# Analog_Teil.net
KiCad netlist of a schematic drawn in EAGLE
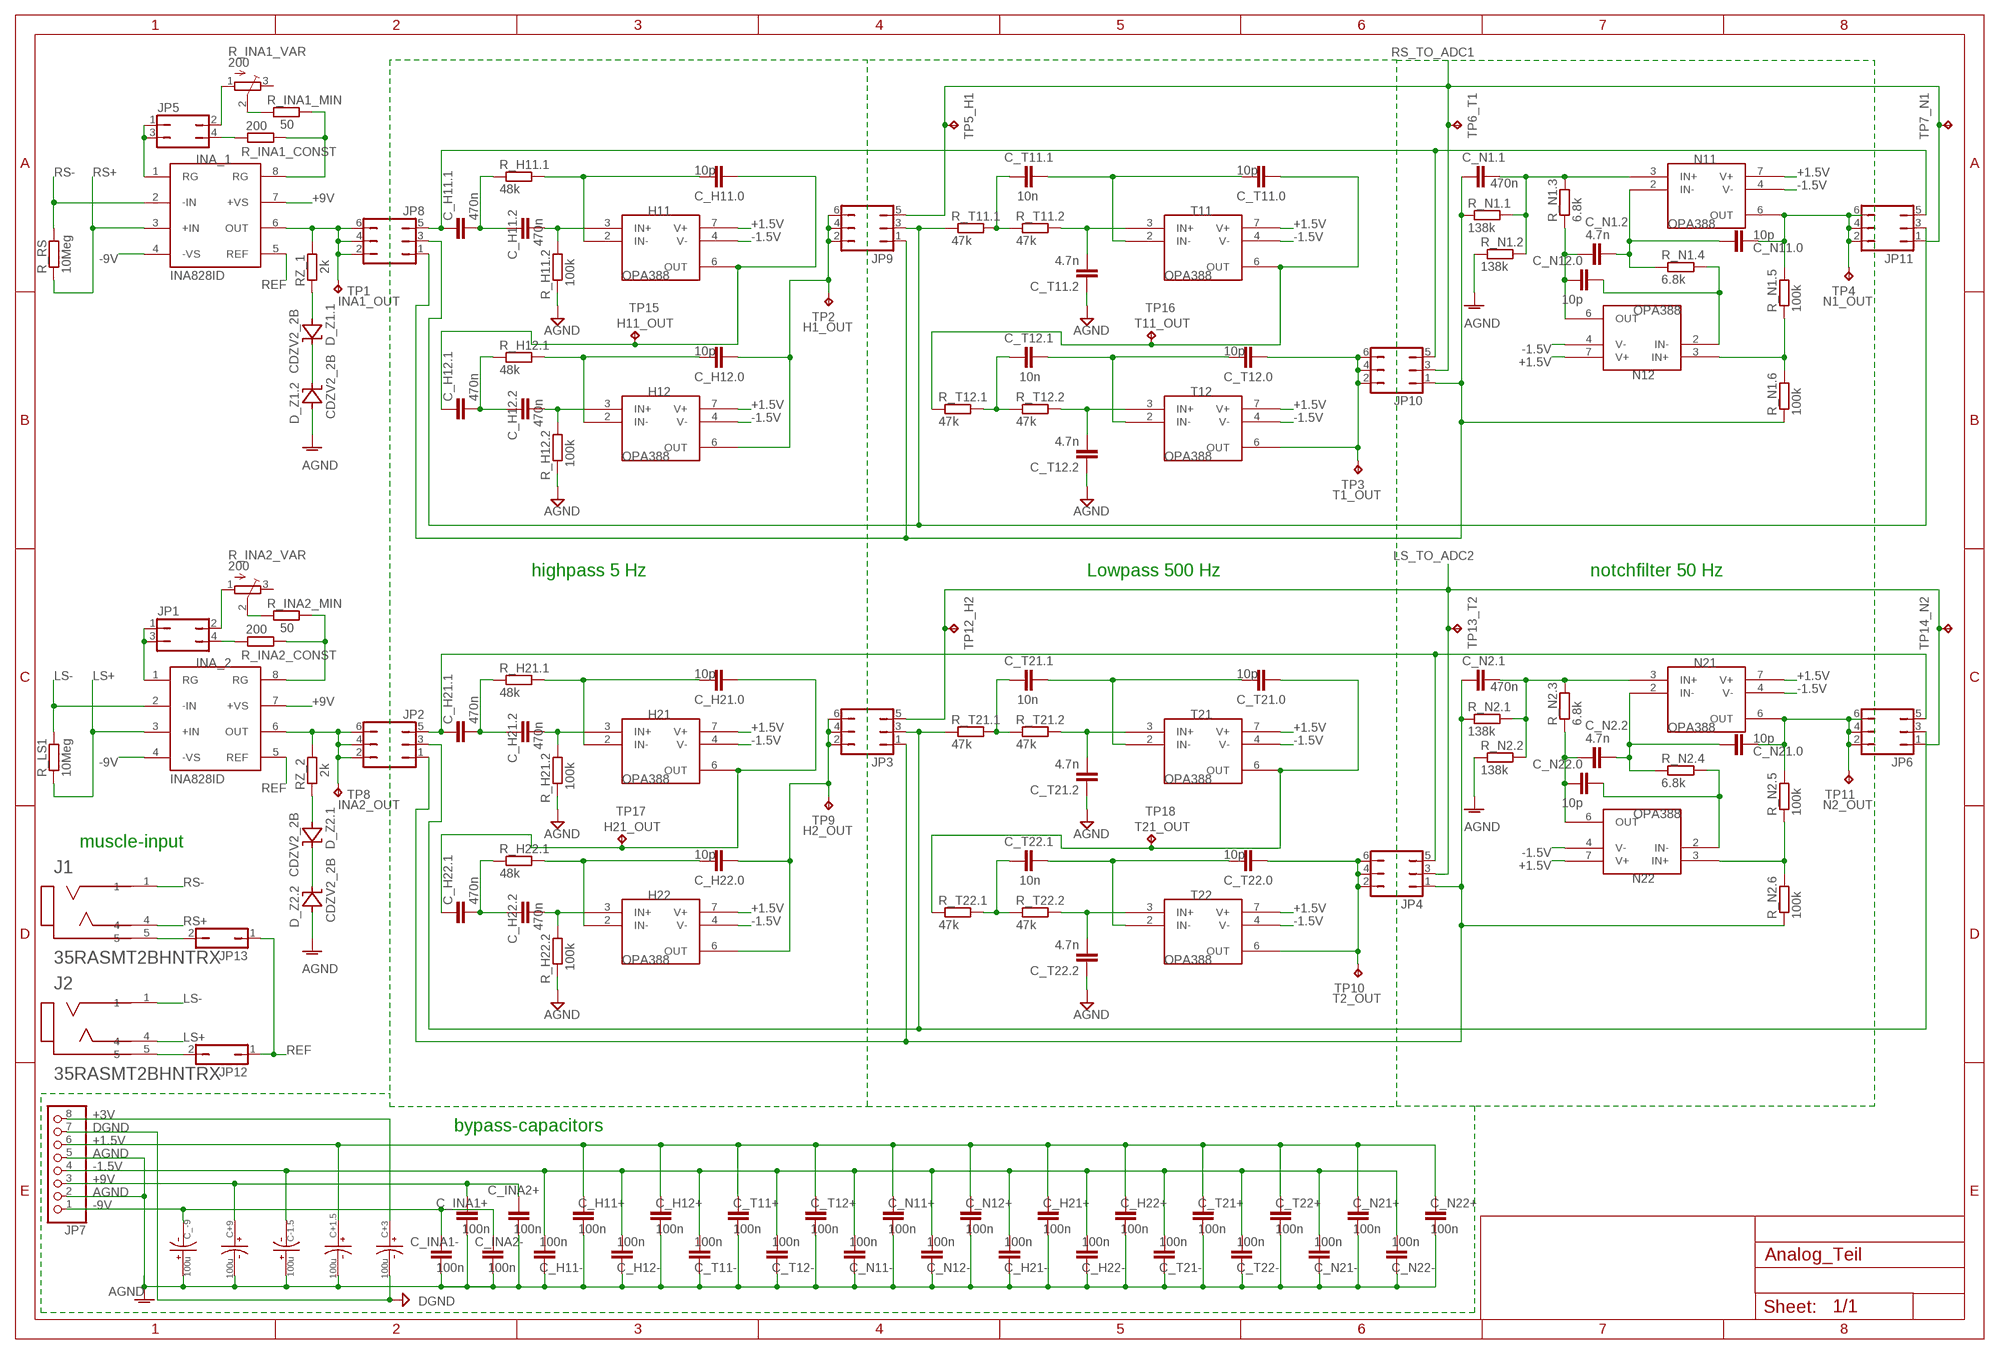
[diagram p0: schematic, sheet 1]

(export (version "E")
  (design (tool "Eeschema 10.0.6"))
  (components
    (comp (ref "C+1.5")
      (value "100u")
      (footprint "eagle-import:CAPPRD350W60D800H1150B")
      (fields (field (name "MF") "Panasonic Electronic") (field (name "MP") "ECA1HM101"))
      (libsource (lib "eagle-import") (part "ECA-1HM101"))
    )
    (comp (ref "C+3")
      (value "100u")
      (footprint "eagle-import:CAPPRD350W60D800H1150B")
      (fields (field (name "MF") "Panasonic Electronic") (field (name "MP") "ECA1HM101"))
      (libsource (lib "eagle-import") (part "ECA-1HM101"))
    )
    (comp (ref "C+9")
      (value "100u")
      (footprint "eagle-import:CAPPRD350W60D800H1150B")
      (fields (field (name "MF") "Panasonic Electronic") (field (name "MP") "ECA1HM101"))
      (libsource (lib "eagle-import") (part "ECA-1HM101"))
    )
    (comp (ref "C-1.5")
      (value "100u")
      (footprint "eagle-import:CAPPRD350W60D800H1150B")
      (fields (field (name "MF") "Panasonic Electronic") (field (name "MP") "ECA1HM101"))
      (libsource (lib "eagle-import") (part "ECA-1HM101"))
    )
    (comp (ref "C_-9")
      (value "100u")
      (footprint "eagle-import:CAPPRD350W60D800H1150B")
      (fields (field (name "MF") "Panasonic Electronic") (field (name "MP") "ECA1HM101"))
      (libsource (lib "eagle-import") (part "ECA-1HM101"))
    )
    (comp (ref "C_H11+")
      (value "100n")
      (footprint "eagle-import:C0805")
      (libsource (lib "eagle-import") (part "C-EUC0805"))
    )
    (comp (ref "C_H11-")
      (value "100n")
      (footprint "eagle-import:C0805")
      (libsource (lib "eagle-import") (part "C-EUC0805"))
    )
    (comp (ref "C_H11.0")
      (value "10p")
      (footprint "eagle-import:C0805")
      (libsource (lib "eagle-import") (part "C-EUC0805"))
    )
    (comp (ref "C_H11.1")
      (value "470n")
      (footprint "eagle-import:C0805")
      (libsource (lib "eagle-import") (part "C-EUC0805"))
    )
    (comp (ref "C_H11.2")
      (value "470n")
      (footprint "eagle-import:C0805")
      (libsource (lib "eagle-import") (part "C-EUC0805"))
    )
    (comp (ref "C_H12+")
      (value "100n")
      (footprint "eagle-import:C0805")
      (libsource (lib "eagle-import") (part "C-EUC0805"))
    )
    (comp (ref "C_H12-")
      (value "100n")
      (footprint "eagle-import:C0805")
      (libsource (lib "eagle-import") (part "C-EUC0805"))
    )
    (comp (ref "C_H12.0")
      (value "10p")
      (footprint "eagle-import:C0805")
      (libsource (lib "eagle-import") (part "C-EUC0805"))
    )
    (comp (ref "C_H12.1")
      (value "470n")
      (footprint "eagle-import:C0805")
      (libsource (lib "eagle-import") (part "C-EUC0805"))
    )
    (comp (ref "C_H12.2")
      (value "470n")
      (footprint "eagle-import:C0805")
      (libsource (lib "eagle-import") (part "C-EUC0805"))
    )
    (comp (ref "C_H21+")
      (value "100n")
      (footprint "eagle-import:C0805")
      (libsource (lib "eagle-import") (part "C-EUC0805"))
    )
    (comp (ref "C_H21-")
      (value "100n")
      (footprint "eagle-import:C0805")
      (libsource (lib "eagle-import") (part "C-EUC0805"))
    )
    (comp (ref "C_H21.0")
      (value "10p")
      (footprint "eagle-import:C0805")
      (libsource (lib "eagle-import") (part "C-EUC0805"))
    )
    (comp (ref "C_H21.1")
      (value "470n")
      (footprint "eagle-import:C0805")
      (libsource (lib "eagle-import") (part "C-EUC0805"))
    )
    (comp (ref "C_H21.2")
      (value "470n")
      (footprint "eagle-import:C0805")
      (libsource (lib "eagle-import") (part "C-EUC0805"))
    )
    (comp (ref "C_H22+")
      (value "100n")
      (footprint "eagle-import:C0805")
      (libsource (lib "eagle-import") (part "C-EUC0805"))
    )
    (comp (ref "C_H22-")
      (value "100n")
      (footprint "eagle-import:C0805")
      (libsource (lib "eagle-import") (part "C-EUC0805"))
    )
    (comp (ref "C_H22.0")
      (value "10p")
      (footprint "eagle-import:C0805")
      (libsource (lib "eagle-import") (part "C-EUC0805"))
    )
    (comp (ref "C_H22.1")
      (value "470n")
      (footprint "eagle-import:C0805")
      (libsource (lib "eagle-import") (part "C-EUC0805"))
    )
    (comp (ref "C_H22.2")
      (value "470n")
      (footprint "eagle-import:C0805")
      (libsource (lib "eagle-import") (part "C-EUC0805"))
    )
    (comp (ref "C_INA1+")
      (value "100n")
      (footprint "eagle-import:C0805")
      (libsource (lib "eagle-import") (part "C-EUC0805"))
    )
    (comp (ref "C_INA1-")
      (value "100n")
      (footprint "eagle-import:C0805")
      (libsource (lib "eagle-import") (part "C-EUC0805"))
    )
    (comp (ref "C_INA2+")
      (value "100n")
      (footprint "eagle-import:C0805")
      (libsource (lib "eagle-import") (part "C-EUC0805"))
    )
    (comp (ref "C_INA2-")
      (value "100n")
      (footprint "eagle-import:C0805")
      (libsource (lib "eagle-import") (part "C-EUC0805"))
    )
    (comp (ref "C_N1.1")
      (value "470n")
      (footprint "eagle-import:C0805")
      (libsource (lib "eagle-import") (part "C-EUC0805"))
    )
    (comp (ref "C_N1.2")
      (value "4.7n")
      (footprint "eagle-import:C0805")
      (libsource (lib "eagle-import") (part "C-EUC0805"))
    )
    (comp (ref "C_N2.1")
      (value "470n")
      (footprint "eagle-import:C0805")
      (libsource (lib "eagle-import") (part "C-EUC0805"))
    )
    (comp (ref "C_N2.2")
      (value "4.7n")
      (footprint "eagle-import:C0805")
      (libsource (lib "eagle-import") (part "C-EUC0805"))
    )
    (comp (ref "C_N11+")
      (value "100n")
      (footprint "eagle-import:C0805")
      (libsource (lib "eagle-import") (part "C-EUC0805"))
    )
    (comp (ref "C_N11-")
      (value "100n")
      (footprint "eagle-import:C0805")
      (libsource (lib "eagle-import") (part "C-EUC0805"))
    )
    (comp (ref "C_N11.0")
      (value "10p")
      (footprint "eagle-import:C0805")
      (libsource (lib "eagle-import") (part "C-EUC0805"))
    )
    (comp (ref "C_N12+")
      (value "100n")
      (footprint "eagle-import:C0805")
      (libsource (lib "eagle-import") (part "C-EUC0805"))
    )
    (comp (ref "C_N12-")
      (value "100n")
      (footprint "eagle-import:C0805")
      (libsource (lib "eagle-import") (part "C-EUC0805"))
    )
    (comp (ref "C_N12.0")
      (value "10p")
      (footprint "eagle-import:C0805")
      (libsource (lib "eagle-import") (part "C-EUC0805"))
    )
    (comp (ref "C_N21+")
      (value "100n")
      (footprint "eagle-import:C0805")
      (libsource (lib "eagle-import") (part "C-EUC0805"))
    )
    (comp (ref "C_N21-")
      (value "100n")
      (footprint "eagle-import:C0805")
      (libsource (lib "eagle-import") (part "C-EUC0805"))
    )
    (comp (ref "C_N21.0")
      (value "10p")
      (footprint "eagle-import:C0805")
      (libsource (lib "eagle-import") (part "C-EUC0805"))
    )
    (comp (ref "C_N22+")
      (value "100n")
      (footprint "eagle-import:C0805")
      (libsource (lib "eagle-import") (part "C-EUC0805"))
    )
    (comp (ref "C_N22-")
      (value "100n")
      (footprint "eagle-import:C0805")
      (libsource (lib "eagle-import") (part "C-EUC0805"))
    )
    (comp (ref "C_N22.0")
      (value "10p")
      (footprint "eagle-import:C0805")
      (libsource (lib "eagle-import") (part "C-EUC0805"))
    )
    (comp (ref "C_T11+")
      (value "100n")
      (footprint "eagle-import:C0805")
      (libsource (lib "eagle-import") (part "C-EUC0805"))
    )
    (comp (ref "C_T11-")
      (value "100n")
      (footprint "eagle-import:C0805")
      (libsource (lib "eagle-import") (part "C-EUC0805"))
    )
    (comp (ref "C_T11.0")
      (value "10p")
      (footprint "eagle-import:C0805")
      (libsource (lib "eagle-import") (part "C-EUC0805"))
    )
    (comp (ref "C_T11.1")
      (value "10n")
      (footprint "eagle-import:C0805")
      (libsource (lib "eagle-import") (part "C-EUC0805"))
    )
    (comp (ref "C_T11.2")
      (value "4.7n")
      (footprint "eagle-import:C0805")
      (libsource (lib "eagle-import") (part "C-EUC0805"))
    )
    (comp (ref "C_T12+")
      (value "100n")
      (footprint "eagle-import:C0805")
      (libsource (lib "eagle-import") (part "C-EUC0805"))
    )
    (comp (ref "C_T12-")
      (value "100n")
      (footprint "eagle-import:C0805")
      (libsource (lib "eagle-import") (part "C-EUC0805"))
    )
    (comp (ref "C_T12.0")
      (value "10p")
      (footprint "eagle-import:C0805")
      (libsource (lib "eagle-import") (part "C-EUC0805"))
    )
    (comp (ref "C_T12.1")
      (value "10n")
      (footprint "eagle-import:C0805")
      (libsource (lib "eagle-import") (part "C-EUC0805"))
    )
    (comp (ref "C_T12.2")
      (value "4.7n")
      (footprint "eagle-import:C0805")
      (libsource (lib "eagle-import") (part "C-EUC0805"))
    )
    (comp (ref "C_T21+")
      (value "100n")
      (footprint "eagle-import:C0805")
      (libsource (lib "eagle-import") (part "C-EUC0805"))
    )
    (comp (ref "C_T21-")
      (value "100n")
      (footprint "eagle-import:C0805")
      (libsource (lib "eagle-import") (part "C-EUC0805"))
    )
    (comp (ref "C_T21.0")
      (value "10p")
      (footprint "eagle-import:C0805")
      (libsource (lib "eagle-import") (part "C-EUC0805"))
    )
    (comp (ref "C_T21.1")
      (value "10n")
      (footprint "eagle-import:C0805")
      (libsource (lib "eagle-import") (part "C-EUC0805"))
    )
    (comp (ref "C_T21.2")
      (value "4.7n")
      (footprint "eagle-import:C0805")
      (libsource (lib "eagle-import") (part "C-EUC0805"))
    )
    (comp (ref "C_T22+")
      (value "100n")
      (footprint "eagle-import:C0805")
      (libsource (lib "eagle-import") (part "C-EUC0805"))
    )
    (comp (ref "C_T22-")
      (value "100n")
      (footprint "eagle-import:C0805")
      (libsource (lib "eagle-import") (part "C-EUC0805"))
    )
    (comp (ref "C_T22.0")
      (value "10p")
      (footprint "eagle-import:C0805")
      (libsource (lib "eagle-import") (part "C-EUC0805"))
    )
    (comp (ref "C_T22.1")
      (value "10n")
      (footprint "eagle-import:C0805")
      (libsource (lib "eagle-import") (part "C-EUC0805"))
    )
    (comp (ref "C_T22.2")
      (value "4.7n")
      (footprint "eagle-import:C0805")
      (libsource (lib "eagle-import") (part "C-EUC0805"))
    )
    (comp (ref "D_Z1.1")
      (value "CDZV2_2B")
      (footprint "eagle-import:SODFL1006X40N")
      (libsource (lib "eagle-import") (part "CDZV2_2BSOD923"))
    )
    (comp (ref "D_Z1.2")
      (value "CDZV2_2B")
      (footprint "eagle-import:SODFL1006X40N")
      (libsource (lib "eagle-import") (part "CDZV2_2BSOD923"))
    )
    (comp (ref "D_Z2.1")
      (value "CDZV2_2B")
      (footprint "eagle-import:SODFL1006X40N")
      (libsource (lib "eagle-import") (part "CDZV2_2BSOD923"))
    )
    (comp (ref "D_Z2.2")
      (value "CDZV2_2B")
      (footprint "eagle-import:SODFL1006X40N")
      (libsource (lib "eagle-import") (part "CDZV2_2BSOD923"))
    )
    (comp (ref "H11")
      (value "OPA388")
      (footprint "eagle-import:SOIC127P600X175-8N")
      (libsource (lib "eagle-import") (part "OPA388"))
    )
    (comp (ref "H12")
      (value "OPA388")
      (footprint "eagle-import:SOIC127P600X175-8N")
      (libsource (lib "eagle-import") (part "OPA388"))
    )
    (comp (ref "H21")
      (value "OPA388")
      (footprint "eagle-import:SOIC127P600X175-8N")
      (libsource (lib "eagle-import") (part "OPA388"))
    )
    (comp (ref "H22")
      (value "OPA388")
      (footprint "eagle-import:SOIC127P600X175-8N")
      (libsource (lib "eagle-import") (part "OPA388"))
    )
    (comp (ref "INA_1")
      (value "INA828ID")
      (footprint "eagle-import:SOIC8")
      (fields (field (name "DIGI-KEY_PART_NUMBER") "296-47415-ND") (field (name "MF") "Texas Instruments"))
      (libsource (lib "eagle-import") (part "INA828ID"))
    )
    (comp (ref "INA_2")
      (value "INA828ID")
      (footprint "eagle-import:SOIC8")
      (fields (field (name "DIGI-KEY_PART_NUMBER") "296-47415-ND") (field (name "MF") "Texas Instruments"))
      (libsource (lib "eagle-import") (part "INA828ID"))
    )
    (comp (ref "J1")
      (value "35RASMT2BHNTRX")
      (footprint "eagle-import:SWITCHCRAFT_35RASMT2BHNTRX")
      (fields (field (name "MF") "Switchcraft"))
      (libsource (lib "eagle-import") (part "35RASMT2BHNTRX"))
    )
    (comp (ref "J2")
      (value "35RASMT2BHNTRX")
      (footprint "eagle-import:SWITCHCRAFT_35RASMT2BHNTRX")
      (fields (field (name "MF") "Switchcraft"))
      (libsource (lib "eagle-import") (part "35RASMT2BHNTRX"))
    )
    (comp (ref "JP1")
      (value "JP2Q")
      (footprint "eagle-import:JP2Q")
      (libsource (lib "eagle-import") (part "JP2Q"))
    )
    (comp (ref "JP2")
      (value "JP3Q")
      (footprint "eagle-import:JP3Q")
      (libsource (lib "eagle-import") (part "JP3Q"))
    )
    (comp (ref "JP3")
      (value "JP3Q")
      (footprint "eagle-import:JP3Q")
      (libsource (lib "eagle-import") (part "JP3Q"))
    )
    (comp (ref "JP4")
      (value "JP3Q")
      (footprint "eagle-import:JP3Q")
      (libsource (lib "eagle-import") (part "JP3Q"))
    )
    (comp (ref "JP5")
      (value "JP2Q")
      (footprint "eagle-import:JP2Q")
      (libsource (lib "eagle-import") (part "JP2Q"))
    )
    (comp (ref "JP6")
      (value "JP3Q")
      (footprint "eagle-import:JP3Q")
      (libsource (lib "eagle-import") (part "JP3Q"))
    )
    (comp (ref "JP7")
      (value "PINHD-1X8")
      (footprint "eagle-import:1X08")
      (libsource (lib "eagle-import") (part "PINHD-1X8"))
    )
    (comp (ref "JP8")
      (value "JP3Q")
      (footprint "eagle-import:JP3Q")
      (libsource (lib "eagle-import") (part "JP3Q"))
    )
    (comp (ref "JP9")
      (value "JP3Q")
      (footprint "eagle-import:JP3Q")
      (libsource (lib "eagle-import") (part "JP3Q"))
    )
    (comp (ref "JP10")
      (value "JP3Q")
      (footprint "eagle-import:JP3Q")
      (libsource (lib "eagle-import") (part "JP3Q"))
    )
    (comp (ref "JP11")
      (value "JP3Q")
      (footprint "eagle-import:JP3Q")
      (libsource (lib "eagle-import") (part "JP3Q"))
    )
    (comp (ref "JP12")
      (value "JP1Q")
      (footprint "eagle-import:JP1")
      (libsource (lib "eagle-import") (part "JP1Q"))
    )
    (comp (ref "JP13")
      (value "JP1Q")
      (footprint "eagle-import:JP1")
      (libsource (lib "eagle-import") (part "JP1Q"))
    )
    (comp (ref "N11")
      (value "OPA388")
      (footprint "eagle-import:SOIC127P600X175-8N")
      (libsource (lib "eagle-import") (part "OPA388"))
    )
    (comp (ref "N12")
      (value "OPA388")
      (footprint "eagle-import:SOIC127P600X175-8N")
      (libsource (lib "eagle-import") (part "OPA388"))
    )
    (comp (ref "N21")
      (value "OPA388")
      (footprint "eagle-import:SOIC127P600X175-8N")
      (libsource (lib "eagle-import") (part "OPA388"))
    )
    (comp (ref "N22")
      (value "OPA388")
      (footprint "eagle-import:SOIC127P600X175-8N")
      (libsource (lib "eagle-import") (part "OPA388"))
    )
    (comp (ref "RZ_1")
      (value "2k")
      (footprint "eagle-import:R0805")
      (libsource (lib "eagle-import") (part "R-EU_R0805"))
    )
    (comp (ref "RZ_2")
      (value "2k")
      (footprint "eagle-import:R0805")
      (libsource (lib "eagle-import") (part "R-EU_R0805"))
    )
    (comp (ref "R_H11.1")
      (value "48k")
      (footprint "eagle-import:R0805")
      (libsource (lib "eagle-import") (part "R-EU_R0805"))
    )
    (comp (ref "R_H11.2")
      (value "100k")
      (footprint "eagle-import:R0805")
      (libsource (lib "eagle-import") (part "R-EU_R0805"))
    )
    (comp (ref "R_H12.1")
      (value "48k")
      (footprint "eagle-import:R0805")
      (libsource (lib "eagle-import") (part "R-EU_R0805"))
    )
    (comp (ref "R_H12.2")
      (value "100k")
      (footprint "eagle-import:R0805")
      (libsource (lib "eagle-import") (part "R-EU_R0805"))
    )
    (comp (ref "R_H21.1")
      (value "48k")
      (footprint "eagle-import:R0805")
      (libsource (lib "eagle-import") (part "R-EU_R0805"))
    )
    (comp (ref "R_H21.2")
      (value "100k")
      (footprint "eagle-import:R0805")
      (libsource (lib "eagle-import") (part "R-EU_R0805"))
    )
    (comp (ref "R_H22.1")
      (value "48k")
      (footprint "eagle-import:R0805")
      (libsource (lib "eagle-import") (part "R-EU_R0805"))
    )
    (comp (ref "R_H22.2")
      (value "100k")
      (footprint "eagle-import:R0805")
      (libsource (lib "eagle-import") (part "R-EU_R0805"))
    )
    (comp (ref "R_INA1_CONST")
      (value "200")
      (footprint "eagle-import:R0805")
      (libsource (lib "eagle-import") (part "R-EU_R0805"))
    )
    (comp (ref "R_INA1_MIN")
      (value "50")
      (footprint "eagle-import:R0805")
      (libsource (lib "eagle-import") (part "R-EU_R0805"))
    )
    (comp (ref "R_INA1_VAR")
      (value "200")
      (footprint "eagle-import:SM-42_43W")
      (fields (field (name "SPICEPREFIX") "J"))
      (libsource (lib "eagle-import") (part "TRIM_EU-SM-42/43W"))
    )
    (comp (ref "R_INA2_CONST")
      (value "200")
      (footprint "eagle-import:R0805")
      (libsource (lib "eagle-import") (part "R-EU_R0805"))
    )
    (comp (ref "R_INA2_MIN")
      (value "50")
      (footprint "eagle-import:R0805")
      (libsource (lib "eagle-import") (part "R-EU_R0805"))
    )
    (comp (ref "R_INA2_VAR")
      (value "200")
      (footprint "eagle-import:SM-42_43W")
      (fields (field (name "SPICEPREFIX") "J"))
      (libsource (lib "eagle-import") (part "TRIM_EU-SM-42/43W"))
    )
    (comp (ref "R_LS1")
      (value "10Meg")
      (footprint "eagle-import:R0805")
      (libsource (lib "eagle-import") (part "R-EU_R0805"))
    )
    (comp (ref "R_N1.1")
      (value "138k")
      (footprint "eagle-import:R0805")
      (libsource (lib "eagle-import") (part "R-EU_R0805"))
    )
    (comp (ref "R_N1.2")
      (value "138k")
      (footprint "eagle-import:R0805")
      (libsource (lib "eagle-import") (part "R-EU_R0805"))
    )
    (comp (ref "R_N1.3")
      (value "6.8k")
      (footprint "eagle-import:R0805")
      (libsource (lib "eagle-import") (part "R-EU_R0805"))
    )
    (comp (ref "R_N1.4")
      (value "6.8k")
      (footprint "eagle-import:R0805")
      (libsource (lib "eagle-import") (part "R-EU_R0805"))
    )
    (comp (ref "R_N1.5")
      (value "100k")
      (footprint "eagle-import:R0805")
      (libsource (lib "eagle-import") (part "R-EU_R0805"))
    )
    (comp (ref "R_N1.6")
      (value "100k")
      (footprint "eagle-import:R0805")
      (libsource (lib "eagle-import") (part "R-EU_R0805"))
    )
    (comp (ref "R_N2.1")
      (value "138k")
      (footprint "eagle-import:R0805")
      (libsource (lib "eagle-import") (part "R-EU_R0805"))
    )
    (comp (ref "R_N2.2")
      (value "138k")
      (footprint "eagle-import:R0805")
      (libsource (lib "eagle-import") (part "R-EU_R0805"))
    )
    (comp (ref "R_N2.3")
      (value "6.8k")
      (footprint "eagle-import:R0805")
      (libsource (lib "eagle-import") (part "R-EU_R0805"))
    )
    (comp (ref "R_N2.4")
      (value "6.8k")
      (footprint "eagle-import:R0805")
      (libsource (lib "eagle-import") (part "R-EU_R0805"))
    )
    (comp (ref "R_N2.5")
      (value "100k")
      (footprint "eagle-import:R0805")
      (libsource (lib "eagle-import") (part "R-EU_R0805"))
    )
    (comp (ref "R_N2.6")
      (value "100k")
      (footprint "eagle-import:R0805")
      (libsource (lib "eagle-import") (part "R-EU_R0805"))
    )
    (comp (ref "R_RS")
      (value "10Meg")
      (footprint "eagle-import:R0805")
      (libsource (lib "eagle-import") (part "R-EU_R0805"))
    )
    (comp (ref "R_T11.1")
      (value "47k")
      (footprint "eagle-import:R0805")
      (libsource (lib "eagle-import") (part "R-EU_R0805"))
    )
    (comp (ref "R_T11.2")
      (value "47k")
      (footprint "eagle-import:R0805")
      (libsource (lib "eagle-import") (part "R-EU_R0805"))
    )
    (comp (ref "R_T12.1")
      (value "47k")
      (footprint "eagle-import:R0805")
      (libsource (lib "eagle-import") (part "R-EU_R0805"))
    )
    (comp (ref "R_T12.2")
      (value "47k")
      (footprint "eagle-import:R0805")
      (libsource (lib "eagle-import") (part "R-EU_R0805"))
    )
    (comp (ref "R_T21.1")
      (value "47k")
      (footprint "eagle-import:R0805")
      (libsource (lib "eagle-import") (part "R-EU_R0805"))
    )
    (comp (ref "R_T21.2")
      (value "47k")
      (footprint "eagle-import:R0805")
      (libsource (lib "eagle-import") (part "R-EU_R0805"))
    )
    (comp (ref "R_T22.1")
      (value "47k")
      (footprint "eagle-import:R0805")
      (libsource (lib "eagle-import") (part "R-EU_R0805"))
    )
    (comp (ref "R_T22.2")
      (value "47k")
      (footprint "eagle-import:R0805")
      (libsource (lib "eagle-import") (part "R-EU_R0805"))
    )
    (comp (ref "T11")
      (value "OPA388")
      (footprint "eagle-import:SOIC127P600X175-8N")
      (libsource (lib "eagle-import") (part "OPA388"))
    )
    (comp (ref "T12")
      (value "OPA388")
      (footprint "eagle-import:SOIC127P600X175-8N")
      (libsource (lib "eagle-import") (part "OPA388"))
    )
    (comp (ref "T21")
      (value "OPA388")
      (footprint "eagle-import:SOIC127P600X175-8N")
      (libsource (lib "eagle-import") (part "OPA388"))
    )
    (comp (ref "T22")
      (value "OPA388")
      (footprint "eagle-import:SOIC127P600X175-8N")
      (libsource (lib "eagle-import") (part "OPA388"))
    )
    (comp (ref "TP1")
      (value "TPPAD1-13")
      (footprint "eagle-import:P1-13")
      (libsource (lib "eagle-import") (part "TPPAD1-13"))
    )
    (comp (ref "TP2")
      (value "TPPAD1-13")
      (footprint "eagle-import:P1-13")
      (libsource (lib "eagle-import") (part "TPPAD1-13"))
    )
    (comp (ref "TP3")
      (value "TPPAD1-13")
      (footprint "eagle-import:P1-13")
      (libsource (lib "eagle-import") (part "TPPAD1-13"))
    )
    (comp (ref "TP4")
      (value "TPPAD1-13")
      (footprint "eagle-import:P1-13")
      (libsource (lib "eagle-import") (part "TPPAD1-13"))
    )
    (comp (ref "TP5_H1")
      (value "TPPAD1-13")
      (footprint "eagle-import:P1-13")
      (libsource (lib "eagle-import") (part "TPPAD1-13"))
    )
    (comp (ref "TP6_T1")
      (value "TPPAD1-13")
      (footprint "eagle-import:P1-13")
      (libsource (lib "eagle-import") (part "TPPAD1-13"))
    )
    (comp (ref "TP7_N1")
      (value "TPPAD1-13")
      (footprint "eagle-import:P1-13")
      (libsource (lib "eagle-import") (part "TPPAD1-13"))
    )
    (comp (ref "TP8")
      (value "TPPAD1-13")
      (footprint "eagle-import:P1-13")
      (libsource (lib "eagle-import") (part "TPPAD1-13"))
    )
    (comp (ref "TP9")
      (value "TPPAD1-13")
      (footprint "eagle-import:P1-13")
      (libsource (lib "eagle-import") (part "TPPAD1-13"))
    )
    (comp (ref "TP10")
      (value "TPPAD1-13")
      (footprint "eagle-import:P1-13")
      (libsource (lib "eagle-import") (part "TPPAD1-13"))
    )
    (comp (ref "TP11")
      (value "TPPAD1-13")
      (footprint "eagle-import:P1-13")
      (libsource (lib "eagle-import") (part "TPPAD1-13"))
    )
    (comp (ref "TP12_H2")
      (value "TPPAD1-13")
      (footprint "eagle-import:P1-13")
      (libsource (lib "eagle-import") (part "TPPAD1-13"))
    )
    (comp (ref "TP13_T2")
      (value "TPPAD1-13")
      (footprint "eagle-import:P1-13")
      (libsource (lib "eagle-import") (part "TPPAD1-13"))
    )
    (comp (ref "TP14_N2")
      (value "TPPAD1-13")
      (footprint "eagle-import:P1-13")
      (libsource (lib "eagle-import") (part "TPPAD1-13"))
    )
    (comp (ref "TP15")
      (value "TPPAD1-13")
      (footprint "eagle-import:P1-13")
      (libsource (lib "eagle-import") (part "TPPAD1-13"))
    )
    (comp (ref "TP16")
      (value "TPPAD1-13")
      (footprint "eagle-import:P1-13")
      (libsource (lib "eagle-import") (part "TPPAD1-13"))
    )
    (comp (ref "TP17")
      (value "TPPAD1-13")
      (footprint "eagle-import:P1-13")
      (libsource (lib "eagle-import") (part "TPPAD1-13"))
    )
    (comp (ref "TP18")
      (value "TPPAD1-13")
      (footprint "eagle-import:P1-13")
      (libsource (lib "eagle-import") (part "TPPAD1-13"))
    )
  )
  (nets
    (net (code "1") (name "/+1.5V") (class "Default")
      (node (ref "C+1.5") (pin "+") (pinfunction "+_+") (pintype "passive"))
      (node (ref "C_H11+") (pin "1") (pinfunction "1_1") (pintype "passive"))
      (node (ref "C_H12+") (pin "1") (pinfunction "1_1") (pintype "passive"))
      (node (ref "C_H21+") (pin "1") (pinfunction "1_1") (pintype "passive"))
      (node (ref "C_H22+") (pin "1") (pinfunction "1_1") (pintype "passive"))
      (node (ref "C_N11+") (pin "1") (pinfunction "1_1") (pintype "passive"))
      (node (ref "C_N12+") (pin "1") (pinfunction "1_1") (pintype "passive"))
      (node (ref "C_N21+") (pin "1") (pinfunction "1_1") (pintype "passive"))
      (node (ref "C_N22+") (pin "1") (pinfunction "1_1") (pintype "passive"))
      (node (ref "C_T11+") (pin "1") (pinfunction "1_1") (pintype "passive"))
      (node (ref "C_T12+") (pin "1") (pinfunction "1_1") (pintype "passive"))
      (node (ref "C_T21+") (pin "1") (pinfunction "1_1") (pintype "passive"))
      (node (ref "C_T22+") (pin "1") (pinfunction "1_1") (pintype "passive"))
      (node (ref "H11") (pin "7") (pinfunction "V+_7") (pintype "power_in"))
      (node (ref "H12") (pin "7") (pinfunction "V+_7") (pintype "power_in"))
      (node (ref "H21") (pin "7") (pinfunction "V+_7") (pintype "power_in"))
      (node (ref "H22") (pin "7") (pinfunction "V+_7") (pintype "power_in"))
      (node (ref "JP7") (pin "6") (pinfunction "6_6") (pintype "passive"))
      (node (ref "N11") (pin "7") (pinfunction "V+_7") (pintype "power_in"))
      (node (ref "N12") (pin "7") (pinfunction "V+_7") (pintype "power_in"))
      (node (ref "N21") (pin "7") (pinfunction "V+_7") (pintype "power_in"))
      (node (ref "N22") (pin "7") (pinfunction "V+_7") (pintype "power_in"))
      (node (ref "T11") (pin "7") (pinfunction "V+_7") (pintype "power_in"))
      (node (ref "T12") (pin "7") (pinfunction "V+_7") (pintype "power_in"))
      (node (ref "T21") (pin "7") (pinfunction "V+_7") (pintype "power_in"))
      (node (ref "T22") (pin "7") (pinfunction "V+_7") (pintype "power_in"))
    )
    (net (code "2") (name "/+3V") (class "Default")
      (node (ref "C+3") (pin "+") (pinfunction "+_+") (pintype "passive"))
      (node (ref "JP7") (pin "8") (pinfunction "8_8") (pintype "passive"))
    )
    (net (code "3") (name "/+9V") (class "Default")
      (node (ref "C+9") (pin "+") (pinfunction "+_+") (pintype "passive"))
      (node (ref "C_INA1+") (pin "1") (pinfunction "1_1") (pintype "passive"))
      (node (ref "C_INA2+") (pin "1") (pinfunction "1_1") (pintype "passive"))
      (node (ref "INA_1") (pin "7") (pinfunction "+VS_7") (pintype "bidirectional"))
      (node (ref "INA_2") (pin "7") (pinfunction "+VS_7") (pintype "bidirectional"))
      (node (ref "JP7") (pin "3") (pinfunction "3_3") (pintype "passive"))
    )
    (net (code "4") (name "/-1.5V") (class "Default")
      (node (ref "C-1.5") (pin "-") (pinfunction "-_-") (pintype "passive"))
      (node (ref "C_H11-") (pin "2") (pinfunction "2_2") (pintype "passive"))
      (node (ref "C_H12-") (pin "2") (pinfunction "2_2") (pintype "passive"))
      (node (ref "C_H21-") (pin "2") (pinfunction "2_2") (pintype "passive"))
      (node (ref "C_H22-") (pin "2") (pinfunction "2_2") (pintype "passive"))
      (node (ref "C_N11-") (pin "2") (pinfunction "2_2") (pintype "passive"))
      (node (ref "C_N12-") (pin "2") (pinfunction "2_2") (pintype "passive"))
      (node (ref "C_N21-") (pin "2") (pinfunction "2_2") (pintype "passive"))
      (node (ref "C_N22-") (pin "2") (pinfunction "2_2") (pintype "passive"))
      (node (ref "C_T11-") (pin "2") (pinfunction "2_2") (pintype "passive"))
      (node (ref "C_T12-") (pin "2") (pinfunction "2_2") (pintype "passive"))
      (node (ref "C_T21-") (pin "2") (pinfunction "2_2") (pintype "passive"))
      (node (ref "C_T22-") (pin "2") (pinfunction "2_2") (pintype "passive"))
      (node (ref "H11") (pin "4") (pinfunction "V-_4") (pintype "power_in"))
      (node (ref "H12") (pin "4") (pinfunction "V-_4") (pintype "power_in"))
      (node (ref "H21") (pin "4") (pinfunction "V-_4") (pintype "power_in"))
      (node (ref "H22") (pin "4") (pinfunction "V-_4") (pintype "power_in"))
      (node (ref "JP7") (pin "4") (pinfunction "4_4") (pintype "passive"))
      (node (ref "N11") (pin "4") (pinfunction "V-_4") (pintype "power_in"))
      (node (ref "N12") (pin "4") (pinfunction "V-_4") (pintype "power_in"))
      (node (ref "N21") (pin "4") (pinfunction "V-_4") (pintype "power_in"))
      (node (ref "N22") (pin "4") (pinfunction "V-_4") (pintype "power_in"))
      (node (ref "T11") (pin "4") (pinfunction "V-_4") (pintype "power_in"))
      (node (ref "T12") (pin "4") (pinfunction "V-_4") (pintype "power_in"))
      (node (ref "T21") (pin "4") (pinfunction "V-_4") (pintype "power_in"))
      (node (ref "T22") (pin "4") (pinfunction "V-_4") (pintype "power_in"))
    )
    (net (code "5") (name "/-9V") (class "Default")
      (node (ref "C_-9") (pin "-") (pinfunction "-_-") (pintype "passive"))
      (node (ref "C_INA1-") (pin "1") (pinfunction "1_1") (pintype "passive"))
      (node (ref "C_INA2-") (pin "1") (pinfunction "1_1") (pintype "passive"))
      (node (ref "INA_1") (pin "4") (pinfunction "-VS_4") (pintype "bidirectional"))
      (node (ref "INA_2") (pin "4") (pinfunction "-VS_4") (pintype "bidirectional"))
      (node (ref "JP7") (pin "1") (pinfunction "1_1") (pintype "passive"))
    )
    (net (code "6") (name "/H1_OUT") (class "Default")
      (node (ref "C_H12.0") (pin "1") (pinfunction "1_1") (pintype "passive"))
      (node (ref "H12") (pin "6") (pinfunction "OUT_6") (pintype "output"))
      (node (ref "JP9") (pin "2") (pinfunction "2_2") (pintype "passive"))
      (node (ref "JP9") (pin "4") (pinfunction "4_4") (pintype "passive"))
      (node (ref "JP9") (pin "6") (pinfunction "6_6") (pintype "passive"))
      (node (ref "TP2") (pin "TP") (pinfunction "TP_TP") (pintype "input"))
    )
    (net (code "7") (name "/H2_OUT") (class "Default")
      (node (ref "C_H22.0") (pin "1") (pinfunction "1_1") (pintype "passive"))
      (node (ref "H22") (pin "6") (pinfunction "OUT_6") (pintype "output"))
      (node (ref "JP3") (pin "2") (pinfunction "2_2") (pintype "passive"))
      (node (ref "JP3") (pin "4") (pinfunction "4_4") (pintype "passive"))
      (node (ref "JP3") (pin "6") (pinfunction "6_6") (pintype "passive"))
      (node (ref "TP9") (pin "TP") (pinfunction "TP_TP") (pintype "input"))
    )
    (net (code "8") (name "/H11_OUT") (class "Default")
      (node (ref "C_H11.0") (pin "1") (pinfunction "1_1") (pintype "passive"))
      (node (ref "C_H12.1") (pin "1") (pinfunction "1_1") (pintype "passive"))
      (node (ref "H11") (pin "6") (pinfunction "OUT_6") (pintype "output"))
      (node (ref "TP15") (pin "TP") (pinfunction "TP_TP") (pintype "input"))
    )
    (net (code "9") (name "/H21_OUT") (class "Default")
      (node (ref "C_H21.0") (pin "1") (pinfunction "1_1") (pintype "passive"))
      (node (ref "C_H22.1") (pin "1") (pinfunction "1_1") (pintype "passive"))
      (node (ref "H21") (pin "6") (pinfunction "OUT_6") (pintype "output"))
      (node (ref "TP17") (pin "TP") (pinfunction "TP_TP") (pintype "input"))
    )
    (net (code "10") (name "/INA1_OUT") (class "Default")
      (node (ref "INA_1") (pin "6") (pinfunction "OUT_6") (pintype "bidirectional"))
      (node (ref "JP8") (pin "2") (pinfunction "2_2") (pintype "passive"))
      (node (ref "JP8") (pin "4") (pinfunction "4_4") (pintype "passive"))
      (node (ref "JP8") (pin "6") (pinfunction "6_6") (pintype "passive"))
      (node (ref "RZ_1") (pin "2") (pinfunction "2_2") (pintype "passive"))
      (node (ref "TP1") (pin "TP") (pinfunction "TP_TP") (pintype "input"))
    )
    (net (code "11") (name "/INA2_OUT") (class "Default")
      (node (ref "INA_2") (pin "6") (pinfunction "OUT_6") (pintype "bidirectional"))
      (node (ref "JP2") (pin "2") (pinfunction "2_2") (pintype "passive"))
      (node (ref "JP2") (pin "4") (pinfunction "4_4") (pintype "passive"))
      (node (ref "JP2") (pin "6") (pinfunction "6_6") (pintype "passive"))
      (node (ref "RZ_2") (pin "2") (pinfunction "2_2") (pintype "passive"))
      (node (ref "TP8") (pin "TP") (pinfunction "TP_TP") (pintype "input"))
    )
    (net (code "12") (name "/LS+") (class "Default")
      (node (ref "INA_2") (pin "3") (pinfunction "+IN_3") (pintype "bidirectional"))
      (node (ref "J2") (pin "4") (pinfunction "4_4") (pintype "passive"))
      (node (ref "R_LS1") (pin "1") (pinfunction "1_1") (pintype "passive"))
    )
    (net (code "13") (name "/LS-") (class "Default")
      (node (ref "INA_2") (pin "2") (pinfunction "-IN_2") (pintype "bidirectional"))
      (node (ref "J2") (pin "1") (pinfunction "1_1") (pintype "passive"))
      (node (ref "R_LS1") (pin "2") (pinfunction "2_2") (pintype "passive"))
    )
    (net (code "14") (name "/LS_TO_ADC2") (class "Default")
      (node (ref "JP3") (pin "5") (pinfunction "5_5") (pintype "passive"))
      (node (ref "JP4") (pin "3") (pinfunction "3_3") (pintype "passive"))
      (node (ref "JP6") (pin "1") (pinfunction "1_1") (pintype "passive"))
      (node (ref "TP12_H2") (pin "TP") (pinfunction "TP_TP") (pintype "input"))
      (node (ref "TP13_T2") (pin "TP") (pinfunction "TP_TP") (pintype "input"))
      (node (ref "TP14_N2") (pin "TP") (pinfunction "TP_TP") (pintype "input"))
    )
    (net (code "15") (name "/N1_OUT") (class "Default")
      (node (ref "C_N11.0") (pin "1") (pinfunction "1_1") (pintype "passive"))
      (node (ref "JP11") (pin "2") (pinfunction "2_2") (pintype "passive"))
      (node (ref "JP11") (pin "4") (pinfunction "4_4") (pintype "passive"))
      (node (ref "JP11") (pin "6") (pinfunction "6_6") (pintype "passive"))
      (node (ref "N11") (pin "6") (pinfunction "OUT_6") (pintype "output"))
      (node (ref "R_N1.5") (pin "2") (pinfunction "2_2") (pintype "passive"))
      (node (ref "TP4") (pin "TP") (pinfunction "TP_TP") (pintype "input"))
    )
    (net (code "16") (name "/N2_OUT") (class "Default")
      (node (ref "C_N21.0") (pin "1") (pinfunction "1_1") (pintype "passive"))
      (node (ref "JP6") (pin "2") (pinfunction "2_2") (pintype "passive"))
      (node (ref "JP6") (pin "4") (pinfunction "4_4") (pintype "passive"))
      (node (ref "JP6") (pin "6") (pinfunction "6_6") (pintype "passive"))
      (node (ref "N21") (pin "6") (pinfunction "OUT_6") (pintype "output"))
      (node (ref "R_N2.5") (pin "2") (pinfunction "2_2") (pintype "passive"))
      (node (ref "TP11") (pin "TP") (pinfunction "TP_TP") (pintype "input"))
    )
    (net (code "17") (name "/REF") (class "Default")
      (node (ref "INA_1") (pin "5") (pinfunction "REF_5") (pintype "bidirectional"))
      (node (ref "INA_2") (pin "5") (pinfunction "REF_5") (pintype "bidirectional"))
      (node (ref "JP12") (pin "1") (pinfunction "1_1") (pintype "passive"))
      (node (ref "JP13") (pin "1") (pinfunction "1_1") (pintype "passive"))
    )
    (net (code "18") (name "/RS+") (class "Default")
      (node (ref "INA_1") (pin "3") (pinfunction "+IN_3") (pintype "bidirectional"))
      (node (ref "J1") (pin "4") (pinfunction "4_4") (pintype "passive"))
      (node (ref "R_RS") (pin "1") (pinfunction "1_1") (pintype "passive"))
    )
    (net (code "19") (name "/RS-") (class "Default")
      (node (ref "INA_1") (pin "2") (pinfunction "-IN_2") (pintype "bidirectional"))
      (node (ref "J1") (pin "1") (pinfunction "1_1") (pintype "passive"))
      (node (ref "R_RS") (pin "2") (pinfunction "2_2") (pintype "passive"))
    )
    (net (code "20") (name "/RS_TO_ADC1") (class "Default")
      (node (ref "JP10") (pin "3") (pinfunction "3_3") (pintype "passive"))
      (node (ref "JP11") (pin "1") (pinfunction "1_1") (pintype "passive"))
      (node (ref "JP9") (pin "5") (pinfunction "5_5") (pintype "passive"))
      (node (ref "TP5_H1") (pin "TP") (pinfunction "TP_TP") (pintype "input"))
      (node (ref "TP6_T1") (pin "TP") (pinfunction "TP_TP") (pintype "input"))
      (node (ref "TP7_N1") (pin "TP") (pinfunction "TP_TP") (pintype "input"))
    )
    (net (code "21") (name "/T1_OUT") (class "Default")
      (node (ref "C_T12.0") (pin "1") (pinfunction "1_1") (pintype "passive"))
      (node (ref "JP10") (pin "2") (pinfunction "2_2") (pintype "passive"))
      (node (ref "JP10") (pin "4") (pinfunction "4_4") (pintype "passive"))
      (node (ref "JP10") (pin "6") (pinfunction "6_6") (pintype "passive"))
      (node (ref "T12") (pin "6") (pinfunction "OUT_6") (pintype "output"))
      (node (ref "TP3") (pin "TP") (pinfunction "TP_TP") (pintype "input"))
    )
    (net (code "22") (name "/T2_OUT") (class "Default")
      (node (ref "C_T22.0") (pin "1") (pinfunction "1_1") (pintype "passive"))
      (node (ref "JP4") (pin "2") (pinfunction "2_2") (pintype "passive"))
      (node (ref "JP4") (pin "4") (pinfunction "4_4") (pintype "passive"))
      (node (ref "JP4") (pin "6") (pinfunction "6_6") (pintype "passive"))
      (node (ref "T22") (pin "6") (pinfunction "OUT_6") (pintype "output"))
      (node (ref "TP10") (pin "TP") (pinfunction "TP_TP") (pintype "input"))
    )
    (net (code "23") (name "/T11_OUT") (class "Default")
      (node (ref "C_T11.0") (pin "1") (pinfunction "1_1") (pintype "passive"))
      (node (ref "R_T12.1") (pin "1") (pinfunction "1_1") (pintype "passive"))
      (node (ref "T11") (pin "6") (pinfunction "OUT_6") (pintype "output"))
      (node (ref "TP16") (pin "TP") (pinfunction "TP_TP") (pintype "input"))
    )
    (net (code "24") (name "/T21_OUT") (class "Default")
      (node (ref "C_T21.0") (pin "1") (pinfunction "1_1") (pintype "passive"))
      (node (ref "R_T22.1") (pin "1") (pinfunction "1_1") (pintype "passive"))
      (node (ref "T21") (pin "6") (pinfunction "OUT_6") (pintype "output"))
      (node (ref "TP18") (pin "TP") (pinfunction "TP_TP") (pintype "input"))
    )
    (net (code "25") (name "AGND") (class "Default")
      (node (ref "C+1.5") (pin "-") (pinfunction "-_-") (pintype "passive"))
      (node (ref "C+9") (pin "-") (pinfunction "-_-") (pintype "passive"))
      (node (ref "C-1.5") (pin "+") (pinfunction "+_+") (pintype "passive"))
      (node (ref "C_-9") (pin "+") (pinfunction "+_+") (pintype "passive"))
      (node (ref "C_H11+") (pin "2") (pinfunction "2_2") (pintype "passive"))
      (node (ref "C_H11-") (pin "1") (pinfunction "1_1") (pintype "passive"))
      (node (ref "C_H12+") (pin "2") (pinfunction "2_2") (pintype "passive"))
      (node (ref "C_H12-") (pin "1") (pinfunction "1_1") (pintype "passive"))
      (node (ref "C_H21+") (pin "2") (pinfunction "2_2") (pintype "passive"))
      (node (ref "C_H21-") (pin "1") (pinfunction "1_1") (pintype "passive"))
      (node (ref "C_H22+") (pin "2") (pinfunction "2_2") (pintype "passive"))
      (node (ref "C_H22-") (pin "1") (pinfunction "1_1") (pintype "passive"))
      (node (ref "C_INA1+") (pin "2") (pinfunction "2_2") (pintype "passive"))
      (node (ref "C_INA1-") (pin "2") (pinfunction "2_2") (pintype "passive"))
      (node (ref "C_INA2+") (pin "2") (pinfunction "2_2") (pintype "passive"))
      (node (ref "C_INA2-") (pin "2") (pinfunction "2_2") (pintype "passive"))
      (node (ref "C_N11+") (pin "2") (pinfunction "2_2") (pintype "passive"))
      (node (ref "C_N11-") (pin "1") (pinfunction "1_1") (pintype "passive"))
      (node (ref "C_N12+") (pin "2") (pinfunction "2_2") (pintype "passive"))
      (node (ref "C_N12-") (pin "1") (pinfunction "1_1") (pintype "passive"))
      (node (ref "C_N21+") (pin "2") (pinfunction "2_2") (pintype "passive"))
      (node (ref "C_N21-") (pin "1") (pinfunction "1_1") (pintype "passive"))
      (node (ref "C_N22+") (pin "2") (pinfunction "2_2") (pintype "passive"))
      (node (ref "C_N22-") (pin "1") (pinfunction "1_1") (pintype "passive"))
      (node (ref "C_T11+") (pin "2") (pinfunction "2_2") (pintype "passive"))
      (node (ref "C_T11-") (pin "1") (pinfunction "1_1") (pintype "passive"))
      (node (ref "C_T11.2") (pin "1") (pinfunction "1_1") (pintype "passive"))
      (node (ref "C_T12+") (pin "2") (pinfunction "2_2") (pintype "passive"))
      (node (ref "C_T12-") (pin "1") (pinfunction "1_1") (pintype "passive"))
      (node (ref "C_T12.2") (pin "1") (pinfunction "1_1") (pintype "passive"))
      (node (ref "C_T21+") (pin "2") (pinfunction "2_2") (pintype "passive"))
      (node (ref "C_T21-") (pin "1") (pinfunction "1_1") (pintype "passive"))
      (node (ref "C_T21.2") (pin "1") (pinfunction "1_1") (pintype "passive"))
      (node (ref "C_T22+") (pin "2") (pinfunction "2_2") (pintype "passive"))
      (node (ref "C_T22-") (pin "1") (pinfunction "1_1") (pintype "passive"))
      (node (ref "C_T22.2") (pin "1") (pinfunction "1_1") (pintype "passive"))
      (node (ref "D_Z1.2") (pin "1") (pinfunction "A_1") (pintype "passive"))
      (node (ref "D_Z2.2") (pin "1") (pinfunction "A_1") (pintype "passive"))
      (node (ref "JP7") (pin "2") (pinfunction "2_2") (pintype "passive"))
      (node (ref "JP7") (pin "5") (pinfunction "5_5") (pintype "passive"))
      (node (ref "R_H11.2") (pin "1") (pinfunction "1_1") (pintype "passive"))
      (node (ref "R_H12.2") (pin "1") (pinfunction "1_1") (pintype "passive"))
      (node (ref "R_H21.2") (pin "1") (pinfunction "1_1") (pintype "passive"))
      (node (ref "R_H22.2") (pin "1") (pinfunction "1_1") (pintype "passive"))
      (node (ref "R_N1.2") (pin "1") (pinfunction "1_1") (pintype "passive"))
      (node (ref "R_N2.2") (pin "1") (pinfunction "1_1") (pintype "passive"))
    )
    (net (code "26") (name "DGND") (class "Default")
      (node (ref "C+3") (pin "-") (pinfunction "-_-") (pintype "passive"))
      (node (ref "JP7") (pin "7") (pinfunction "7_7") (pintype "passive"))
    )
    (net (code "27") (name "Net-(C_H11.1-Pad1)") (class "Default")
      (node (ref "C_H11.1") (pin "1") (pinfunction "1_1") (pintype "passive"))
      (node (ref "JP10") (pin "5") (pinfunction "5_5") (pintype "passive"))
      (node (ref "JP11") (pin "5") (pinfunction "5_5") (pintype "passive"))
      (node (ref "JP8") (pin "5") (pinfunction "5_5") (pintype "passive"))
    )
    (net (code "28") (name "Net-(C_H11.1-Pad2)") (class "Default")
      (node (ref "C_H11.1") (pin "2") (pinfunction "2_2") (pintype "passive"))
      (node (ref "C_H11.2") (pin "1") (pinfunction "1_1") (pintype "passive"))
      (node (ref "R_H11.1") (pin "1") (pinfunction "1_1") (pintype "passive"))
    )
    (net (code "29") (name "Net-(C_H12.1-Pad2)") (class "Default")
      (node (ref "C_H12.1") (pin "2") (pinfunction "2_2") (pintype "passive"))
      (node (ref "C_H12.2") (pin "1") (pinfunction "1_1") (pintype "passive"))
      (node (ref "R_H12.1") (pin "1") (pinfunction "1_1") (pintype "passive"))
    )
    (net (code "30") (name "Net-(C_H21.1-Pad1)") (class "Default")
      (node (ref "C_H21.1") (pin "1") (pinfunction "1_1") (pintype "passive"))
      (node (ref "JP2") (pin "5") (pinfunction "5_5") (pintype "passive"))
      (node (ref "JP4") (pin "5") (pinfunction "5_5") (pintype "passive"))
      (node (ref "JP6") (pin "5") (pinfunction "5_5") (pintype "passive"))
    )
    (net (code "31") (name "Net-(C_H21.1-Pad2)") (class "Default")
      (node (ref "C_H21.1") (pin "2") (pinfunction "2_2") (pintype "passive"))
      (node (ref "C_H21.2") (pin "1") (pinfunction "1_1") (pintype "passive"))
      (node (ref "R_H21.1") (pin "1") (pinfunction "1_1") (pintype "passive"))
    )
    (net (code "32") (name "Net-(C_H22.1-Pad2)") (class "Default")
      (node (ref "C_H22.1") (pin "2") (pinfunction "2_2") (pintype "passive"))
      (node (ref "C_H22.2") (pin "1") (pinfunction "1_1") (pintype "passive"))
      (node (ref "R_H22.1") (pin "1") (pinfunction "1_1") (pintype "passive"))
    )
    (net (code "33") (name "Net-(C_N1.1-Pad1)") (class "Default")
      (node (ref "C_N1.1") (pin "1") (pinfunction "1_1") (pintype "passive"))
      (node (ref "JP10") (pin "1") (pinfunction "1_1") (pintype "passive"))
      (node (ref "JP8") (pin "1") (pinfunction "1_1") (pintype "passive"))
      (node (ref "JP9") (pin "1") (pinfunction "1_1") (pintype "passive"))
      (node (ref "R_N1.1") (pin "1") (pinfunction "1_1") (pintype "passive"))
      (node (ref "R_N1.6") (pin "1") (pinfunction "1_1") (pintype "passive"))
    )
    (net (code "34") (name "Net-(C_N2.1-Pad1)") (class "Default")
      (node (ref "C_N2.1") (pin "1") (pinfunction "1_1") (pintype "passive"))
      (node (ref "JP2") (pin "1") (pinfunction "1_1") (pintype "passive"))
      (node (ref "JP3") (pin "1") (pinfunction "1_1") (pintype "passive"))
      (node (ref "JP4") (pin "1") (pinfunction "1_1") (pintype "passive"))
      (node (ref "R_N2.1") (pin "1") (pinfunction "1_1") (pintype "passive"))
      (node (ref "R_N2.6") (pin "1") (pinfunction "1_1") (pintype "passive"))
    )
    (net (code "35") (name "Net-(C_T11.1-Pad1)") (class "Default")
      (node (ref "C_T11.1") (pin "1") (pinfunction "1_1") (pintype "passive"))
      (node (ref "R_T11.1") (pin "2") (pinfunction "2_2") (pintype "passive"))
      (node (ref "R_T11.2") (pin "1") (pinfunction "1_1") (pintype "passive"))
    )
    (net (code "36") (name "Net-(C_T12.1-Pad1)") (class "Default")
      (node (ref "C_T12.1") (pin "1") (pinfunction "1_1") (pintype "passive"))
      (node (ref "R_T12.1") (pin "2") (pinfunction "2_2") (pintype "passive"))
      (node (ref "R_T12.2") (pin "1") (pinfunction "1_1") (pintype "passive"))
    )
    (net (code "37") (name "Net-(C_T21.1-Pad1)") (class "Default")
      (node (ref "C_T21.1") (pin "1") (pinfunction "1_1") (pintype "passive"))
      (node (ref "R_T21.1") (pin "2") (pinfunction "2_2") (pintype "passive"))
      (node (ref "R_T21.2") (pin "1") (pinfunction "1_1") (pintype "passive"))
    )
    (net (code "38") (name "Net-(C_T22.1-Pad1)") (class "Default")
      (node (ref "C_T22.1") (pin "1") (pinfunction "1_1") (pintype "passive"))
      (node (ref "R_T22.1") (pin "2") (pinfunction "2_2") (pintype "passive"))
      (node (ref "R_T22.2") (pin "1") (pinfunction "1_1") (pintype "passive"))
    )
    (net (code "39") (name "Net-(D_Z1.1-A)") (class "Default")
      (node (ref "D_Z1.1") (pin "1") (pinfunction "A_1") (pintype "passive"))
      (node (ref "RZ_1") (pin "1") (pinfunction "1_1") (pintype "passive"))
    )
    (net (code "40") (name "Net-(D_Z1.1-C)") (class "Default")
      (node (ref "D_Z1.1") (pin "2") (pinfunction "C_2") (pintype "passive"))
      (node (ref "D_Z1.2") (pin "2") (pinfunction "C_2") (pintype "passive"))
    )
    (net (code "41") (name "Net-(D_Z2.1-A)") (class "Default")
      (node (ref "D_Z2.1") (pin "1") (pinfunction "A_1") (pintype "passive"))
      (node (ref "RZ_2") (pin "1") (pinfunction "1_1") (pintype "passive"))
    )
    (net (code "42") (name "Net-(D_Z2.1-C)") (class "Default")
      (node (ref "D_Z2.1") (pin "2") (pinfunction "C_2") (pintype "passive"))
      (node (ref "D_Z2.2") (pin "2") (pinfunction "C_2") (pintype "passive"))
    )
    (net (code "43") (name "Net-(H11-IN+)") (class "Default")
      (node (ref "C_H11.2") (pin "2") (pinfunction "2_2") (pintype "passive"))
      (node (ref "H11") (pin "3") (pinfunction "IN+_3") (pintype "input"))
      (node (ref "R_H11.2") (pin "2") (pinfunction "2_2") (pintype "passive"))
    )
    (net (code "44") (name "Net-(H11-IN-)") (class "Default")
      (node (ref "C_H11.0") (pin "2") (pinfunction "2_2") (pintype "passive"))
      (node (ref "H11") (pin "2") (pinfunction "IN-_2") (pintype "input"))
      (node (ref "R_H11.1") (pin "2") (pinfunction "2_2") (pintype "passive"))
    )
    (net (code "45") (name "Net-(H12-IN+)") (class "Default")
      (node (ref "C_H12.2") (pin "2") (pinfunction "2_2") (pintype "passive"))
      (node (ref "H12") (pin "3") (pinfunction "IN+_3") (pintype "input"))
      (node (ref "R_H12.2") (pin "2") (pinfunction "2_2") (pintype "passive"))
    )
    (net (code "46") (name "Net-(H12-IN-)") (class "Default")
      (node (ref "C_H12.0") (pin "2") (pinfunction "2_2") (pintype "passive"))
      (node (ref "H12") (pin "2") (pinfunction "IN-_2") (pintype "input"))
      (node (ref "R_H12.1") (pin "2") (pinfunction "2_2") (pintype "passive"))
    )
    (net (code "47") (name "Net-(H21-IN+)") (class "Default")
      (node (ref "C_H21.2") (pin "2") (pinfunction "2_2") (pintype "passive"))
      (node (ref "H21") (pin "3") (pinfunction "IN+_3") (pintype "input"))
      (node (ref "R_H21.2") (pin "2") (pinfunction "2_2") (pintype "passive"))
    )
    (net (code "48") (name "Net-(H21-IN-)") (class "Default")
      (node (ref "C_H21.0") (pin "2") (pinfunction "2_2") (pintype "passive"))
      (node (ref "H21") (pin "2") (pinfunction "IN-_2") (pintype "input"))
      (node (ref "R_H21.1") (pin "2") (pinfunction "2_2") (pintype "passive"))
    )
    (net (code "49") (name "Net-(H22-IN+)") (class "Default")
      (node (ref "C_H22.2") (pin "2") (pinfunction "2_2") (pintype "passive"))
      (node (ref "H22") (pin "3") (pinfunction "IN+_3") (pintype "input"))
      (node (ref "R_H22.2") (pin "2") (pinfunction "2_2") (pintype "passive"))
    )
    (net (code "50") (name "Net-(H22-IN-)") (class "Default")
      (node (ref "C_H22.0") (pin "2") (pinfunction "2_2") (pintype "passive"))
      (node (ref "H22") (pin "2") (pinfunction "IN-_2") (pintype "input"))
      (node (ref "R_H22.1") (pin "2") (pinfunction "2_2") (pintype "passive"))
    )
    (net (code "51") (name "Net-(INA_1-RG-Pad1)") (class "Default")
      (node (ref "INA_1") (pin "1") (pinfunction "RG_1") (pintype "bidirectional"))
      (node (ref "JP5") (pin "1") (pinfunction "1_1") (pintype "passive"))
      (node (ref "JP5") (pin "3") (pinfunction "3_3") (pintype "passive"))
    )
    (net (code "52") (name "Net-(INA_1-RG-Pad8)") (class "Default")
      (node (ref "INA_1") (pin "8") (pinfunction "RG_8") (pintype "bidirectional"))
      (node (ref "R_INA1_CONST") (pin "2") (pinfunction "2_2") (pintype "passive"))
      (node (ref "R_INA1_MIN") (pin "2") (pinfunction "2_2") (pintype "passive"))
    )
    (net (code "53") (name "Net-(INA_2-RG-Pad1)") (class "Default")
      (node (ref "INA_2") (pin "1") (pinfunction "RG_1") (pintype "bidirectional"))
      (node (ref "JP1") (pin "1") (pinfunction "1_1") (pintype "passive"))
      (node (ref "JP1") (pin "3") (pinfunction "3_3") (pintype "passive"))
    )
    (net (code "54") (name "Net-(INA_2-RG-Pad8)") (class "Default")
      (node (ref "INA_2") (pin "8") (pinfunction "RG_8") (pintype "bidirectional"))
      (node (ref "R_INA2_CONST") (pin "2") (pinfunction "2_2") (pintype "passive"))
      (node (ref "R_INA2_MIN") (pin "2") (pinfunction "2_2") (pintype "passive"))
    )
    (net (code "55") (name "Net-(J1-Pad5)") (class "Default")
      (node (ref "J1") (pin "5") (pinfunction "5_5") (pintype "passive"))
      (node (ref "JP13") (pin "2") (pinfunction "2_2") (pintype "passive"))
    )
    (net (code "56") (name "Net-(J2-Pad5)") (class "Default")
      (node (ref "J2") (pin "5") (pinfunction "5_5") (pintype "passive"))
      (node (ref "JP12") (pin "2") (pinfunction "2_2") (pintype "passive"))
    )
    (net (code "57") (name "Net-(JP1-Pad4)") (class "Default")
      (node (ref "JP1") (pin "4") (pinfunction "4_4") (pintype "passive"))
      (node (ref "R_INA2_CONST") (pin "1") (pinfunction "1_1") (pintype "passive"))
    )
    (net (code "58") (name "Net-(JP2-Pad3)") (class "Default")
      (node (ref "JP2") (pin "3") (pinfunction "3_3") (pintype "passive"))
      (node (ref "JP3") (pin "3") (pinfunction "3_3") (pintype "passive"))
      (node (ref "JP6") (pin "3") (pinfunction "3_3") (pintype "passive"))
      (node (ref "R_T21.1") (pin "1") (pinfunction "1_1") (pintype "passive"))
    )
    (net (code "59") (name "Net-(JP5-Pad4)") (class "Default")
      (node (ref "JP5") (pin "4") (pinfunction "4_4") (pintype "passive"))
      (node (ref "R_INA1_CONST") (pin "1") (pinfunction "1_1") (pintype "passive"))
    )
    (net (code "60") (name "Net-(JP11-Pad3)") (class "Default")
      (node (ref "JP11") (pin "3") (pinfunction "3_3") (pintype "passive"))
      (node (ref "JP8") (pin "3") (pinfunction "3_3") (pintype "passive"))
      (node (ref "JP9") (pin "3") (pinfunction "3_3") (pintype "passive"))
      (node (ref "R_T11.1") (pin "1") (pinfunction "1_1") (pintype "passive"))
    )
    (net (code "61") (name "Net-(N11-IN+)") (class "Default")
      (node (ref "C_N1.1") (pin "2") (pinfunction "2_2") (pintype "passive"))
      (node (ref "N11") (pin "3") (pinfunction "IN+_3") (pintype "input"))
      (node (ref "R_N1.1") (pin "2") (pinfunction "2_2") (pintype "passive"))
      (node (ref "R_N1.2") (pin "2") (pinfunction "2_2") (pintype "passive"))
      (node (ref "R_N1.3") (pin "2") (pinfunction "2_2") (pintype "passive"))
    )
    (net (code "62") (name "Net-(N11-IN-)") (class "Default")
      (node (ref "C_N1.2") (pin "2") (pinfunction "2_2") (pintype "passive"))
      (node (ref "C_N11.0") (pin "2") (pinfunction "2_2") (pintype "passive"))
      (node (ref "N11") (pin "2") (pinfunction "IN-_2") (pintype "input"))
      (node (ref "R_N1.4") (pin "1") (pinfunction "1_1") (pintype "passive"))
    )
    (net (code "63") (name "Net-(N12-IN+)") (class "Default")
      (node (ref "N12") (pin "3") (pinfunction "IN+_3") (pintype "input"))
      (node (ref "R_N1.5") (pin "1") (pinfunction "1_1") (pintype "passive"))
      (node (ref "R_N1.6") (pin "2") (pinfunction "2_2") (pintype "passive"))
    )
    (net (code "64") (name "Net-(N12-IN-)") (class "Default")
      (node (ref "C_N12.0") (pin "1") (pinfunction "1_1") (pintype "passive"))
      (node (ref "N12") (pin "2") (pinfunction "IN-_2") (pintype "input"))
      (node (ref "R_N1.4") (pin "2") (pinfunction "2_2") (pintype "passive"))
    )
    (net (code "65") (name "Net-(N12-OUT)") (class "Default")
      (node (ref "C_N1.2") (pin "1") (pinfunction "1_1") (pintype "passive"))
      (node (ref "C_N12.0") (pin "2") (pinfunction "2_2") (pintype "passive"))
      (node (ref "N12") (pin "6") (pinfunction "OUT_6") (pintype "output"))
      (node (ref "R_N1.3") (pin "1") (pinfunction "1_1") (pintype "passive"))
    )
    (net (code "66") (name "Net-(N21-IN+)") (class "Default")
      (node (ref "C_N2.1") (pin "2") (pinfunction "2_2") (pintype "passive"))
      (node (ref "N21") (pin "3") (pinfunction "IN+_3") (pintype "input"))
      (node (ref "R_N2.1") (pin "2") (pinfunction "2_2") (pintype "passive"))
      (node (ref "R_N2.2") (pin "2") (pinfunction "2_2") (pintype "passive"))
      (node (ref "R_N2.3") (pin "2") (pinfunction "2_2") (pintype "passive"))
    )
    (net (code "67") (name "Net-(N21-IN-)") (class "Default")
      (node (ref "C_N2.2") (pin "2") (pinfunction "2_2") (pintype "passive"))
      (node (ref "C_N21.0") (pin "2") (pinfunction "2_2") (pintype "passive"))
      (node (ref "N21") (pin "2") (pinfunction "IN-_2") (pintype "input"))
      (node (ref "R_N2.4") (pin "1") (pinfunction "1_1") (pintype "passive"))
    )
    (net (code "68") (name "Net-(N22-IN+)") (class "Default")
      (node (ref "N22") (pin "3") (pinfunction "IN+_3") (pintype "input"))
      (node (ref "R_N2.5") (pin "1") (pinfunction "1_1") (pintype "passive"))
      (node (ref "R_N2.6") (pin "2") (pinfunction "2_2") (pintype "passive"))
    )
    (net (code "69") (name "Net-(N22-IN-)") (class "Default")
      (node (ref "C_N22.0") (pin "1") (pinfunction "1_1") (pintype "passive"))
      (node (ref "N22") (pin "2") (pinfunction "IN-_2") (pintype "input"))
      (node (ref "R_N2.4") (pin "2") (pinfunction "2_2") (pintype "passive"))
    )
    (net (code "70") (name "Net-(N22-OUT)") (class "Default")
      (node (ref "C_N2.2") (pin "1") (pinfunction "1_1") (pintype "passive"))
      (node (ref "C_N22.0") (pin "2") (pinfunction "2_2") (pintype "passive"))
      (node (ref "N22") (pin "6") (pinfunction "OUT_6") (pintype "output"))
      (node (ref "R_N2.3") (pin "1") (pinfunction "1_1") (pintype "passive"))
    )
    (net (code "71") (name "Net-(R_INA1_VAR-A)") (class "Default")
      (node (ref "JP5") (pin "2") (pinfunction "2_2") (pintype "passive"))
      (node (ref "R_INA1_VAR") (pin "1") (pinfunction "A_1") (pintype "passive"))
    )
    (net (code "72") (name "Net-(R_INA1_VAR-S)") (class "Default")
      (node (ref "R_INA1_MIN") (pin "1") (pinfunction "1_1") (pintype "passive"))
      (node (ref "R_INA1_VAR") (pin "2") (pinfunction "S_2") (pintype "passive"))
    )
    (net (code "73") (name "Net-(R_INA2_VAR-A)") (class "Default")
      (node (ref "JP1") (pin "2") (pinfunction "2_2") (pintype "passive"))
      (node (ref "R_INA2_VAR") (pin "1") (pinfunction "A_1") (pintype "passive"))
    )
    (net (code "74") (name "Net-(R_INA2_VAR-S)") (class "Default")
      (node (ref "R_INA2_MIN") (pin "1") (pinfunction "1_1") (pintype "passive"))
      (node (ref "R_INA2_VAR") (pin "2") (pinfunction "S_2") (pintype "passive"))
    )
    (net (code "75") (name "Net-(T11-IN+)") (class "Default")
      (node (ref "C_T11.2") (pin "2") (pinfunction "2_2") (pintype "passive"))
      (node (ref "R_T11.2") (pin "2") (pinfunction "2_2") (pintype "passive"))
      (node (ref "T11") (pin "3") (pinfunction "IN+_3") (pintype "input"))
    )
    (net (code "76") (name "Net-(T11-IN-)") (class "Default")
      (node (ref "C_T11.0") (pin "2") (pinfunction "2_2") (pintype "passive"))
      (node (ref "C_T11.1") (pin "2") (pinfunction "2_2") (pintype "passive"))
      (node (ref "T11") (pin "2") (pinfunction "IN-_2") (pintype "input"))
    )
    (net (code "77") (name "Net-(T12-IN+)") (class "Default")
      (node (ref "C_T12.2") (pin "2") (pinfunction "2_2") (pintype "passive"))
      (node (ref "R_T12.2") (pin "2") (pinfunction "2_2") (pintype "passive"))
      (node (ref "T12") (pin "3") (pinfunction "IN+_3") (pintype "input"))
    )
    (net (code "78") (name "Net-(T12-IN-)") (class "Default")
      (node (ref "C_T12.0") (pin "2") (pinfunction "2_2") (pintype "passive"))
      (node (ref "C_T12.1") (pin "2") (pinfunction "2_2") (pintype "passive"))
      (node (ref "T12") (pin "2") (pinfunction "IN-_2") (pintype "input"))
    )
    (net (code "79") (name "Net-(T21-IN+)") (class "Default")
      (node (ref "C_T21.2") (pin "2") (pinfunction "2_2") (pintype "passive"))
      (node (ref "R_T21.2") (pin "2") (pinfunction "2_2") (pintype "passive"))
      (node (ref "T21") (pin "3") (pinfunction "IN+_3") (pintype "input"))
    )
    (net (code "80") (name "Net-(T21-IN-)") (class "Default")
      (node (ref "C_T21.0") (pin "2") (pinfunction "2_2") (pintype "passive"))
      (node (ref "C_T21.1") (pin "2") (pinfunction "2_2") (pintype "passive"))
      (node (ref "T21") (pin "2") (pinfunction "IN-_2") (pintype "input"))
    )
    (net (code "81") (name "Net-(T22-IN+)") (class "Default")
      (node (ref "C_T22.2") (pin "2") (pinfunction "2_2") (pintype "passive"))
      (node (ref "R_T22.2") (pin "2") (pinfunction "2_2") (pintype "passive"))
      (node (ref "T22") (pin "3") (pinfunction "IN+_3") (pintype "input"))
    )
    (net (code "82") (name "Net-(T22-IN-)") (class "Default")
      (node (ref "C_T22.0") (pin "2") (pinfunction "2_2") (pintype "passive"))
      (node (ref "C_T22.1") (pin "2") (pinfunction "2_2") (pintype "passive"))
      (node (ref "T22") (pin "2") (pinfunction "IN-_2") (pintype "input"))
    )
    (net (code "83") (name "unconnected-(H11-NC1-Pad1)") (class "Default")
      (node (ref "H11") (pin "1") (pinfunction "NC1_1") (pintype "no_connect"))
    )
    (net (code "84") (name "unconnected-(H11-NC2-Pad5)") (class "Default")
      (node (ref "H11") (pin "5") (pinfunction "NC2_5") (pintype "no_connect"))
    )
    (net (code "85") (name "unconnected-(H11-NC3-Pad8)") (class "Default")
      (node (ref "H11") (pin "8") (pinfunction "NC3_8") (pintype "no_connect"))
    )
    (net (code "86") (name "unconnected-(H12-NC1-Pad1)") (class "Default")
      (node (ref "H12") (pin "1") (pinfunction "NC1_1") (pintype "no_connect"))
    )
    (net (code "87") (name "unconnected-(H12-NC2-Pad5)") (class "Default")
      (node (ref "H12") (pin "5") (pinfunction "NC2_5") (pintype "no_connect"))
    )
    (net (code "88") (name "unconnected-(H12-NC3-Pad8)") (class "Default")
      (node (ref "H12") (pin "8") (pinfunction "NC3_8") (pintype "no_connect"))
    )
    (net (code "89") (name "unconnected-(H21-NC1-Pad1)") (class "Default")
      (node (ref "H21") (pin "1") (pinfunction "NC1_1") (pintype "no_connect"))
    )
    (net (code "90") (name "unconnected-(H21-NC2-Pad5)") (class "Default")
      (node (ref "H21") (pin "5") (pinfunction "NC2_5") (pintype "no_connect"))
    )
    (net (code "91") (name "unconnected-(H21-NC3-Pad8)") (class "Default")
      (node (ref "H21") (pin "8") (pinfunction "NC3_8") (pintype "no_connect"))
    )
    (net (code "92") (name "unconnected-(H22-NC1-Pad1)") (class "Default")
      (node (ref "H22") (pin "1") (pinfunction "NC1_1") (pintype "no_connect"))
    )
    (net (code "93") (name "unconnected-(H22-NC2-Pad5)") (class "Default")
      (node (ref "H22") (pin "5") (pinfunction "NC2_5") (pintype "no_connect"))
    )
    (net (code "94") (name "unconnected-(H22-NC3-Pad8)") (class "Default")
      (node (ref "H22") (pin "8") (pinfunction "NC3_8") (pintype "no_connect"))
    )
    (net (code "95") (name "unconnected-(N11-NC1-Pad1)") (class "Default")
      (node (ref "N11") (pin "1") (pinfunction "NC1_1") (pintype "no_connect"))
    )
    (net (code "96") (name "unconnected-(N11-NC2-Pad5)") (class "Default")
      (node (ref "N11") (pin "5") (pinfunction "NC2_5") (pintype "no_connect"))
    )
    (net (code "97") (name "unconnected-(N11-NC3-Pad8)") (class "Default")
      (node (ref "N11") (pin "8") (pinfunction "NC3_8") (pintype "no_connect"))
    )
    (net (code "98") (name "unconnected-(N12-NC1-Pad1)") (class "Default")
      (node (ref "N12") (pin "1") (pinfunction "NC1_1") (pintype "no_connect"))
    )
    (net (code "99") (name "unconnected-(N12-NC2-Pad5)") (class "Default")
      (node (ref "N12") (pin "5") (pinfunction "NC2_5") (pintype "no_connect"))
    )
    (net (code "100") (name "unconnected-(N12-NC3-Pad8)") (class "Default")
      (node (ref "N12") (pin "8") (pinfunction "NC3_8") (pintype "no_connect"))
    )
    (net (code "101") (name "unconnected-(N21-NC1-Pad1)") (class "Default")
      (node (ref "N21") (pin "1") (pinfunction "NC1_1") (pintype "no_connect"))
    )
    (net (code "102") (name "unconnected-(N21-NC2-Pad5)") (class "Default")
      (node (ref "N21") (pin "5") (pinfunction "NC2_5") (pintype "no_connect"))
    )
    (net (code "103") (name "unconnected-(N21-NC3-Pad8)") (class "Default")
      (node (ref "N21") (pin "8") (pinfunction "NC3_8") (pintype "no_connect"))
    )
    (net (code "104") (name "unconnected-(N22-NC1-Pad1)") (class "Default")
      (node (ref "N22") (pin "1") (pinfunction "NC1_1") (pintype "no_connect"))
    )
    (net (code "105") (name "unconnected-(N22-NC2-Pad5)") (class "Default")
      (node (ref "N22") (pin "5") (pinfunction "NC2_5") (pintype "no_connect"))
    )
    (net (code "106") (name "unconnected-(N22-NC3-Pad8)") (class "Default")
      (node (ref "N22") (pin "8") (pinfunction "NC3_8") (pintype "no_connect"))
    )
    (net (code "107") (name "unconnected-(R_INA1_VAR-E-Pad3)") (class "Default")
      (node (ref "R_INA1_VAR") (pin "3") (pinfunction "E_3") (pintype "passive"))
    )
    (net (code "108") (name "unconnected-(R_INA2_VAR-E-Pad3)") (class "Default")
      (node (ref "R_INA2_VAR") (pin "3") (pinfunction "E_3") (pintype "passive"))
    )
    (net (code "109") (name "unconnected-(T11-NC1-Pad1)") (class "Default")
      (node (ref "T11") (pin "1") (pinfunction "NC1_1") (pintype "no_connect"))
    )
    (net (code "110") (name "unconnected-(T11-NC2-Pad5)") (class "Default")
      (node (ref "T11") (pin "5") (pinfunction "NC2_5") (pintype "no_connect"))
    )
    (net (code "111") (name "unconnected-(T11-NC3-Pad8)") (class "Default")
      (node (ref "T11") (pin "8") (pinfunction "NC3_8") (pintype "no_connect"))
    )
    (net (code "112") (name "unconnected-(T12-NC1-Pad1)") (class "Default")
      (node (ref "T12") (pin "1") (pinfunction "NC1_1") (pintype "no_connect"))
    )
    (net (code "113") (name "unconnected-(T12-NC2-Pad5)") (class "Default")
      (node (ref "T12") (pin "5") (pinfunction "NC2_5") (pintype "no_connect"))
    )
    (net (code "114") (name "unconnected-(T12-NC3-Pad8)") (class "Default")
      (node (ref "T12") (pin "8") (pinfunction "NC3_8") (pintype "no_connect"))
    )
    (net (code "115") (name "unconnected-(T21-NC1-Pad1)") (class "Default")
      (node (ref "T21") (pin "1") (pinfunction "NC1_1") (pintype "no_connect"))
    )
    (net (code "116") (name "unconnected-(T21-NC2-Pad5)") (class "Default")
      (node (ref "T21") (pin "5") (pinfunction "NC2_5") (pintype "no_connect"))
    )
    (net (code "117") (name "unconnected-(T21-NC3-Pad8)") (class "Default")
      (node (ref "T21") (pin "8") (pinfunction "NC3_8") (pintype "no_connect"))
    )
    (net (code "118") (name "unconnected-(T22-NC1-Pad1)") (class "Default")
      (node (ref "T22") (pin "1") (pinfunction "NC1_1") (pintype "no_connect"))
    )
    (net (code "119") (name "unconnected-(T22-NC2-Pad5)") (class "Default")
      (node (ref "T22") (pin "5") (pinfunction "NC2_5") (pintype "no_connect"))
    )
    (net (code "120") (name "unconnected-(T22-NC3-Pad8)") (class "Default")
      (node (ref "T22") (pin "8") (pinfunction "NC3_8") (pintype "no_connect"))
    )
  )
)
